# MCU.net
KiCad netlist of a schematic drawn in Altium Designer
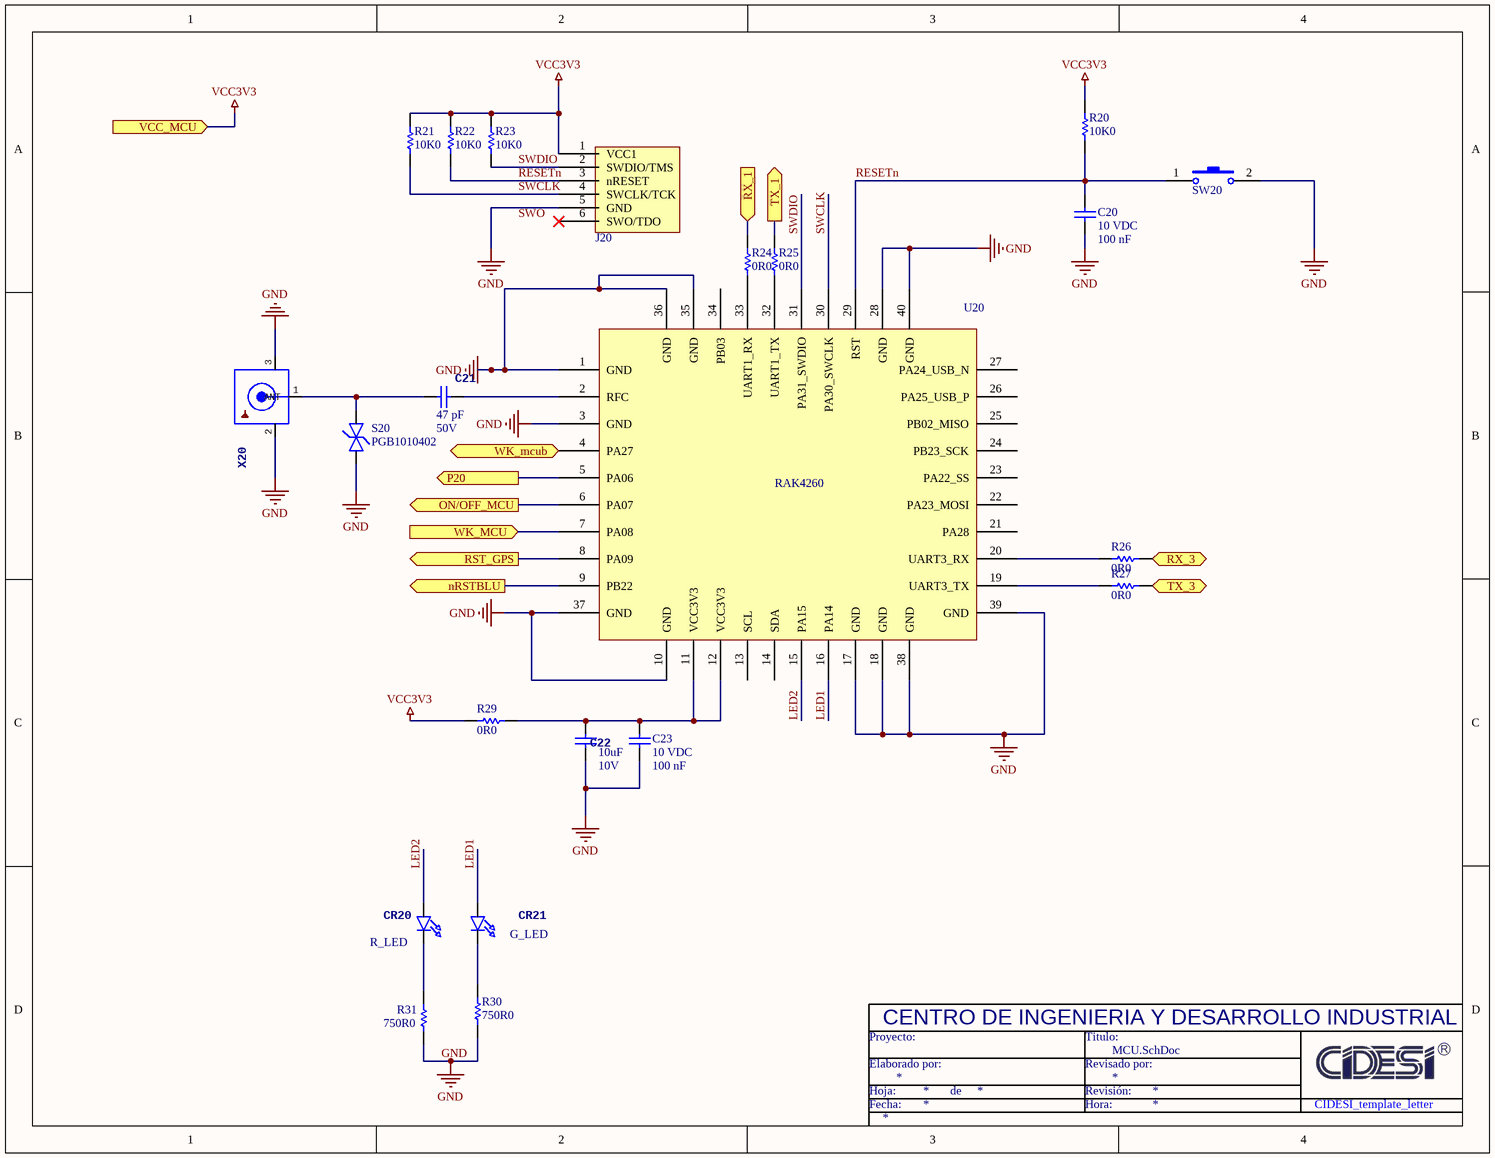
[diagram p0: MCU.SchDoc]

(export (version "E")
  (design (tool "Eeschema 10.0.6"))
  (components
    (comp (ref "C20")
      (value "100 nF, 10 V")
      (footprint "C0402")
      (description "Multilayer Ceramic Capacitors MLCC - SMD/SMT 0402 0.1uF 10volts X7R 10%")
      (fields
        (field (name "MANUFACTURER") "Murata Electronics")
        (field (name "MANUFACTURER PART NUMBER") "GRM155R71A104KA01D")
        (field (name "VOLTAGE RATING DC") "10 VDC")
        (field (name "CAPACITANCE - NF") "100 nF")
      )
      (libsource (lib "PULV3") (part "100 nF, 10 V"))
    )
    (comp (ref "C21")
      (value "GCQ1555C1H470JB01D")
      (footprint "C0402")
      (description "Cap_Cer")
      (fields
        (field (name "MANUFACTURER") "Murata Electronics")
        (field (name "TOLERANCE") "5 %")
        (field (name "CAPACITANCE") "47 pF")
        (field (name "VOLTAGE RATING DC") "50V")
      )
      (libsource (lib "PULV3") (part "47pF, 50V"))
    )
    (comp (ref "C22")
      (value "ZRB15XR61A106ME01D")
      (footprint "C0402")
      (description "Cap_Cer")
      (fields
        (field (name "MANUFACTURER") "Murata Electronics")
        (field (name "TOLERANCE") "20 %")
        (field (name "CAPACITANCE") "10uF")
        (field (name "VOLTAGE RATING DC") "10V")
      )
      (libsource (lib "PULV3") (part "10uF, 10V"))
    )
    (comp (ref "C23")
      (value "100 nF, 10 V")
      (footprint "C0402")
      (description "Multilayer Ceramic Capacitors MLCC - SMD/SMT 0402 0.1uF 10volts X7R 10%")
      (fields
        (field (name "MANUFACTURER") "Murata Electronics")
        (field (name "MANUFACTURER PART NUMBER") "GRM155R71A104KA01D")
        (field (name "VOLTAGE RATING DC") "10 VDC")
        (field (name "CAPACITANCE - NF") "100 nF")
      )
      (libsource (lib "PULV3") (part "100 nF, 10 V"))
    )
    (comp (ref "CR20")
      (value "KO DELLS1.22-KHLI-24")
      (footprint "0603_LED")
      (description "Led_Red")
      (fields
        (field (name "MANUFACTURER") "OSRAM Opto Semiconductors")
        (field (name "MANUFACTURER PART NUMBER") "KR DELPS1.22-UHVI-26-H3Q4")
        (field (name "PRODUCT") "R_LED")
      )
      (libsource (lib "PULV5") (part "Led_Red_0603"))
    )
    (comp (ref "CR21")
      (value "KG DELMS1.22-PHQI-24-E6L6")
      (footprint "0603_LED")
      (description "Led_Green")
      (fields (field (name "MANUFACTURER") "OSRAM Opto Semiconductors") (field (name "PRODUCT") "G_LED"))
      (libsource (lib "PULV5") (part "Led_Green_0603"))
    )
    (comp (ref "J20")
      (value "ICSP")
      (footprint "TC2030-MCP-NL")
      (description "Footprint Programador")
      (fields (field (name "MANUFACTURER PART NUMBER") "No aplica"))
      (libsource (lib "PULV3") (part "ICSP"))
    )
    (comp (ref "R20")
      (value "10K0")
      (footprint "0402_RES")
      (description "Resistor")
      (fields (field (name "MANUFACTURER PART NUMBER") "CRCW040210K0FKTD"))
      (libsource (lib "PULV3") (part "10 KOHM, 63 mW"))
    )
    (comp (ref "R21")
      (value "10K0")
      (footprint "0402_RES")
      (description "Resistor")
      (fields (field (name "MANUFACTURER PART NUMBER") "CRCW040210K0FKTD"))
      (libsource (lib "PULV3") (part "10 KOHM, 63 mW"))
    )
    (comp (ref "R22")
      (value "10K0")
      (footprint "0402_RES")
      (description "Resistor")
      (fields (field (name "MANUFACTURER PART NUMBER") "CRCW040210K0FKTD"))
      (libsource (lib "PULV3") (part "10 KOHM, 63 mW"))
    )
    (comp (ref "R23")
      (value "10K0")
      (footprint "0402_RES")
      (description "Resistor")
      (fields (field (name "MANUFACTURER PART NUMBER") "CRCW040210K0FKTD"))
      (libsource (lib "PULV3") (part "10 KOHM, 63 mW"))
    )
    (comp (ref "R24")
      (value "PANASONIC ELECTRONIC COMPONENTS")
      (footprint "0402_RES")
      (description "Resistor")
      (fields (field (name "MANUFACTURER PART NUMBER") "ERJ-2GE0R00X") (field (name "RESISTANCE") "0R0"))
      (libsource (lib "PULV3") (part "0R0"))
    )
    (comp (ref "R25")
      (value "PANASONIC ELECTRONIC COMPONENTS")
      (footprint "0402_RES")
      (description "Resistor")
      (fields (field (name "MANUFACTURER PART NUMBER") "ERJ-2GE0R00X") (field (name "RESISTANCE") "0R0"))
      (libsource (lib "PULV3") (part "0R0"))
    )
    (comp (ref "R26")
      (value "PANASONIC ELECTRONIC COMPONENTS")
      (footprint "0402_RES")
      (description "Resistor")
      (fields (field (name "MANUFACTURER PART NUMBER") "ERJ-2GE0R00X") (field (name "RESISTANCE") "0R0"))
      (libsource (lib "PULV3") (part "0R0"))
    )
    (comp (ref "R27")
      (value "PANASONIC ELECTRONIC COMPONENTS")
      (footprint "0402_RES")
      (description "Resistor")
      (fields (field (name "MANUFACTURER PART NUMBER") "ERJ-2GE0R00X") (field (name "RESISTANCE") "0R0"))
      (libsource (lib "PULV3") (part "0R0"))
    )
    (comp (ref "R29")
      (value "PANASONIC ELECTRONIC COMPONENTS")
      (footprint "0402_RES")
      (description "Resistor")
      (fields (field (name "MANUFACTURER PART NUMBER") "ERJ-2GE0R00X") (field (name "RESISTANCE") "0R0"))
      (libsource (lib "PULV3") (part "0R0"))
    )
    (comp (ref "R30")
      (value "ERJ-2GEJ751X")
      (footprint "0402_RES")
      (description "Resistor")
      (fields (field (name "MANUFACTURER") "PANASONIC") (field (name "RESISTANCE") "750R0"))
      (libsource (lib "PULV3") (part "750R0, 63mW"))
    )
    (comp (ref "R31")
      (value "ERJ-2GEJ751X")
      (footprint "0402_RES")
      (description "Resistor")
      (fields (field (name "MANUFACTURER") "PANASONIC") (field (name "RESISTANCE") "750R0"))
      (libsource (lib "PULV3") (part "750R0, 63mW"))
    )
    (comp (ref "S20")
      (value "PGB1010402")
      (footprint "Supresor_0402")
      (description "ESD Suppressor")
      (fields
        (field (name "MANUFACTURER") "Littelfuse")
        (field (name "MANUFACTURER PART NUMBER") "PGB1010402KR")
      )
      (libsource (lib "PULV3") (part "PGB1010402"))
    )
    (comp (ref "SW20")
      (value "95C04A3GWRT")
      (footprint "Push Button SMDsin")
      (description "Push Button SMD large")
      (fields (field (name "MANUFACTURER") "Grayhill"))
      (libsource (lib "PULV5") (part "Push Buttom-SMD_large"))
    )
    (comp (ref "U20")
      (value "RAK4260")
      (footprint "RAK4260")
      (description "MODULO LORA")
      (fields (field (name "MANUFACTURER PART NUMBER") "RAK4260 LoRa® Module - US915"))
      (libsource (lib "PULV3") (part "RAK4260"))
    )
    (comp (ref "X20")
      (value "RECE.20279.001E.01")
      (footprint "U.FL")
      (description "Connector UFL")
      (fields (field (name "MANUFACTURER") "Taoglas"))
      (libsource (lib "PULV5") (part "SMACONNECTOR_UFL"))
    )
  )
  (nets
    (net (code "1") (name "/LED1") (class "Default")
      (node (ref "CR21") (pin "A") (pinfunction "A_A") (pintype "passive"))
      (node (ref "U20") (pin "16") (pinfunction "PA14_16") (pintype "passive"))
    )
    (net (code "2") (name "/LED2") (class "Default")
      (node (ref "CR20") (pin "A") (pinfunction "A_A") (pintype "passive"))
      (node (ref "U20") (pin "15") (pinfunction "PA15_15") (pintype "passive"))
    )
    (net (code "3") (name "/ON{slash}OFF_MCU") (class "Default")
      (node (ref "U20") (pin "6") (pinfunction "PA07_6") (pintype "passive"))
    )
    (net (code "4") (name "/P20") (class "Default")
      (node (ref "U20") (pin "5") (pinfunction "PA06_5") (pintype "passive"))
    )
    (net (code "5") (name "/RESETn") (class "Default")
      (node (ref "C20") (pin "1") (pinfunction "1_1") (pintype "passive"))
      (node (ref "J20") (pin "3") (pinfunction "nRESET_3") (pintype "passive"))
      (node (ref "R20") (pin "1") (pinfunction "1_1") (pintype "passive"))
      (node (ref "R22") (pin "1") (pinfunction "1_1") (pintype "passive"))
      (node (ref "SW20") (pin "1") (pinfunction "1_1") (pintype "passive"))
      (node (ref "U20") (pin "29") (pinfunction "RST_29") (pintype "passive"))
    )
    (net (code "6") (name "/RST_GPS") (class "Default")
      (node (ref "U20") (pin "8") (pinfunction "PA09_8") (pintype "passive"))
    )
    (net (code "7") (name "/RX_1") (class "Default")
      (node (ref "R24") (pin "2") (pinfunction "2_2") (pintype "passive"))
    )
    (net (code "8") (name "/RX_3") (class "Default")
      (node (ref "R26") (pin "2") (pinfunction "2_2") (pintype "passive"))
    )
    (net (code "9") (name "/SWCLK") (class "Default")
      (node (ref "J20") (pin "4") (pinfunction "SWCLK/TCK_4") (pintype "passive"))
      (node (ref "R21") (pin "1") (pinfunction "1_1") (pintype "passive"))
      (node (ref "U20") (pin "30") (pinfunction "PA30_SWCLK_30") (pintype "passive"))
    )
    (net (code "10") (name "/SWDIO") (class "Default")
      (node (ref "J20") (pin "2") (pinfunction "SWDIO/TMS_2") (pintype "passive"))
      (node (ref "R23") (pin "1") (pinfunction "1_1") (pintype "passive"))
      (node (ref "U20") (pin "31") (pinfunction "PA31_SWDIO_31") (pintype "passive"))
    )
    (net (code "12") (name "/TX_1") (class "Default")
      (node (ref "R25") (pin "2") (pinfunction "2_2") (pintype "passive"))
    )
    (net (code "13") (name "/TX_3") (class "Default")
      (node (ref "R27") (pin "2") (pinfunction "2_2") (pintype "passive"))
    )
    (net (code "14") (name "/WK_MCU") (class "Default")
      (node (ref "U20") (pin "7") (pinfunction "PA08_7") (pintype "passive"))
    )
    (net (code "15") (name "/WK_mcub") (class "Default")
      (node (ref "U20") (pin "4") (pinfunction "PA27_4") (pintype "passive"))
    )
    (net (code "16") (name "/nRSTBLU") (class "Default")
      (node (ref "U20") (pin "9") (pinfunction "PB22_9") (pintype "passive"))
    )
    (net (code "17") (name "GND") (class "Default")
      (node (ref "C20") (pin "2") (pinfunction "2_2") (pintype "passive"))
      (node (ref "C22") (pin "2") (pinfunction "2_2") (pintype "passive"))
      (node (ref "C23") (pin "2") (pinfunction "2_2") (pintype "passive"))
      (node (ref "J20") (pin "5") (pinfunction "GND_5") (pintype "passive"))
      (node (ref "R30") (pin "1") (pinfunction "1_1") (pintype "passive"))
      (node (ref "R31") (pin "2") (pinfunction "2_2") (pintype "passive"))
      (node (ref "S20") (pin "2") (pinfunction "2_2") (pintype "passive"))
      (node (ref "SW20") (pin "2") (pinfunction "2_2") (pintype "passive"))
      (node (ref "U20") (pin "1") (pinfunction "GND_1") (pintype "passive"))
      (node (ref "U20") (pin "10") (pinfunction "GND_10") (pintype "passive"))
      (node (ref "U20") (pin "17") (pinfunction "GND_17") (pintype "passive"))
      (node (ref "U20") (pin "18") (pinfunction "GND_18") (pintype "passive"))
      (node (ref "U20") (pin "28") (pinfunction "GND_28") (pintype "passive"))
      (node (ref "U20") (pin "3") (pinfunction "GND_3") (pintype "passive"))
      (node (ref "U20") (pin "35") (pinfunction "GND_35") (pintype "passive"))
      (node (ref "U20") (pin "36") (pinfunction "GND_36") (pintype "passive"))
      (node (ref "U20") (pin "37") (pinfunction "GND_37") (pintype "passive"))
      (node (ref "U20") (pin "38") (pinfunction "GND_38") (pintype "passive"))
      (node (ref "U20") (pin "39") (pinfunction "GND_39") (pintype "passive"))
      (node (ref "U20") (pin "40") (pinfunction "GND_40") (pintype "passive"))
      (node (ref "X20") (pin "2") (pinfunction "GND_2") (pintype "power_in"))
      (node (ref "X20") (pin "3") (pinfunction "GND_3") (pintype "power_in"))
    )
    (net (code "18") (name "Net-(C22-Pad1)") (class "Default")
      (node (ref "C22") (pin "1") (pinfunction "1_1") (pintype "passive"))
      (node (ref "C23") (pin "1") (pinfunction "1_1") (pintype "passive"))
      (node (ref "R29") (pin "2") (pinfunction "2_2") (pintype "passive"))
      (node (ref "U20") (pin "11") (pinfunction "VCC3V3_11") (pintype "passive"))
      (node (ref "U20") (pin "12") (pinfunction "VCC3V3_12") (pintype "passive"))
    )
    (net (code "19") (name "Net-(CR20-PadK)") (class "Default")
      (node (ref "CR20") (pin "K") (pinfunction "K_K") (pintype "passive"))
      (node (ref "R31") (pin "1") (pinfunction "1_1") (pintype "passive"))
    )
    (net (code "20") (name "Net-(CR21-PadK)") (class "Default")
      (node (ref "CR21") (pin "K") (pinfunction "K_K") (pintype "passive"))
      (node (ref "R30") (pin "2") (pinfunction "2_2") (pintype "passive"))
    )
    (net (code "21") (name "Net-(U20-RFC)") (class "Default")
      (node (ref "C21") (pin "2") (pinfunction "2_2") (pintype "passive"))
      (node (ref "U20") (pin "2") (pinfunction "RFC_2") (pintype "passive"))
    )
    (net (code "22") (name "Net-(U20-UART1_RX)") (class "Default")
      (node (ref "R24") (pin "1") (pinfunction "1_1") (pintype "passive"))
      (node (ref "U20") (pin "33") (pinfunction "UART1_RX_33") (pintype "passive"))
    )
    (net (code "23") (name "Net-(U20-UART1_TX)") (class "Default")
      (node (ref "R25") (pin "1") (pinfunction "1_1") (pintype "passive"))
      (node (ref "U20") (pin "32") (pinfunction "UART1_TX_32") (pintype "passive"))
    )
    (net (code "24") (name "Net-(U20-UART3_RX)") (class "Default")
      (node (ref "R26") (pin "1") (pinfunction "1_1") (pintype "passive"))
      (node (ref "U20") (pin "20") (pinfunction "UART3_RX_20") (pintype "passive"))
    )
    (net (code "25") (name "Net-(U20-UART3_TX)") (class "Default")
      (node (ref "R27") (pin "1") (pinfunction "1_1") (pintype "passive"))
      (node (ref "U20") (pin "19") (pinfunction "UART3_TX_19") (pintype "passive"))
    )
    (net (code "26") (name "Net-(X20-ANT)") (class "Default")
      (node (ref "C21") (pin "1") (pinfunction "1_1") (pintype "passive"))
      (node (ref "S20") (pin "1") (pinfunction "1_1") (pintype "passive"))
      (node (ref "X20") (pin "1") (pinfunction "ANT_1") (pintype "passive"))
    )
    (net (code "27") (name "VCC3V3") (class "Default")
      (node (ref "J20") (pin "1") (pinfunction "VCC1_1") (pintype "passive"))
      (node (ref "R20") (pin "2") (pinfunction "2_2") (pintype "passive"))
      (node (ref "R21") (pin "2") (pinfunction "2_2") (pintype "passive"))
      (node (ref "R22") (pin "2") (pinfunction "2_2") (pintype "passive"))
      (node (ref "R23") (pin "2") (pinfunction "2_2") (pintype "passive"))
      (node (ref "R29") (pin "1") (pinfunction "1_1") (pintype "passive"))
    )
    (net (code "28") (name "unconnected-(J20-SWO{slash}TDO-Pad6)") (class "Default")
      (node (ref "J20") (pin "6") (pinfunction "SWO/TDO_6") (pintype "passive+no_connect"))
    )
    (net (code "29") (name "unconnected-(U20-PA22_SS-Pad23)") (class "Default")
      (node (ref "U20") (pin "23") (pinfunction "PA22_SS_23") (pintype "passive"))
    )
    (net (code "30") (name "unconnected-(U20-PA23_MOSI-Pad22)") (class "Default")
      (node (ref "U20") (pin "22") (pinfunction "PA23_MOSI_22") (pintype "passive"))
    )
    (net (code "31") (name "unconnected-(U20-PA24_USB_N-Pad27)") (class "Default")
      (node (ref "U20") (pin "27") (pinfunction "PA24_USB_N_27") (pintype "passive"))
    )
    (net (code "32") (name "unconnected-(U20-PA25_USB_P-Pad26)") (class "Default")
      (node (ref "U20") (pin "26") (pinfunction "PA25_USB_P_26") (pintype "passive"))
    )
    (net (code "33") (name "unconnected-(U20-PA28-Pad21)") (class "Default")
      (node (ref "U20") (pin "21") (pinfunction "PA28_21") (pintype "passive"))
    )
    (net (code "34") (name "unconnected-(U20-PB02_MISO-Pad25)") (class "Default")
      (node (ref "U20") (pin "25") (pinfunction "PB02_MISO_25") (pintype "passive"))
    )
    (net (code "35") (name "unconnected-(U20-PB03-Pad34)") (class "Default")
      (node (ref "U20") (pin "34") (pinfunction "PB03_34") (pintype "passive"))
    )
    (net (code "36") (name "unconnected-(U20-PB23_SCK-Pad24)") (class "Default")
      (node (ref "U20") (pin "24") (pinfunction "PB23_SCK_24") (pintype "passive"))
    )
    (net (code "37") (name "unconnected-(U20-SCL-Pad13)") (class "Default")
      (node (ref "U20") (pin "13") (pinfunction "SCL_13") (pintype "passive"))
    )
    (net (code "38") (name "unconnected-(U20-SDA-Pad14)") (class "Default")
      (node (ref "U20") (pin "14") (pinfunction "SDA_14") (pintype "passive"))
    )
  )
)
